# BNO055_SCH.net
KiCad netlist of a schematic drawn in EAGLE
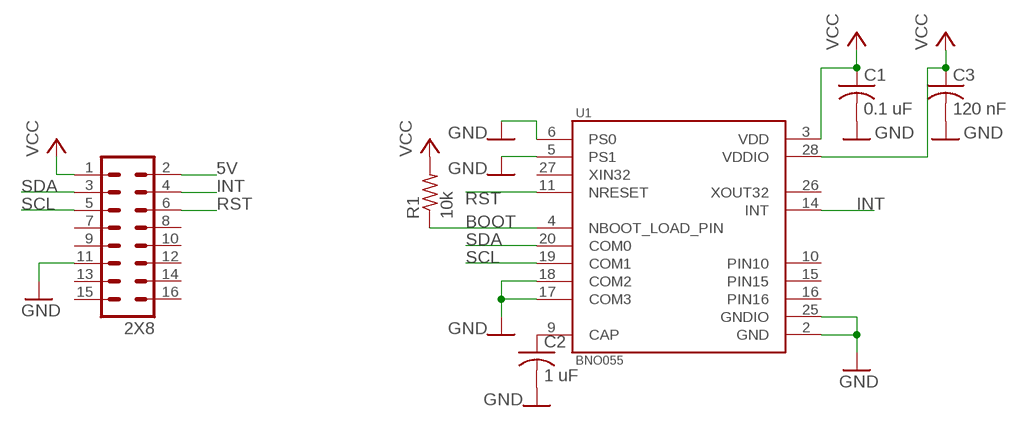
[diagram p0: schematic, sheet 1]

(export (version "E")
  (design (tool "Eeschema 10.0.6"))
  (components
    (comp (ref "2X8")
      (value "MA08-2")
      (footprint "eagle-import:MA08-2")
      (libsource (lib "eagle-import") (part "MA08-2"))
    )
    (comp (ref "C1")
      (value "0.1 uF")
      (footprint "eagle-import:C1206")
      (libsource (lib "eagle-import") (part "C-USC1206"))
    )
    (comp (ref "C2")
      (value "1 uF")
      (footprint "eagle-import:C1206")
      (libsource (lib "eagle-import") (part "C-USC1206"))
    )
    (comp (ref "C3")
      (value "120 nF")
      (footprint "eagle-import:C1206")
      (libsource (lib "eagle-import") (part "C-USC1206"))
    )
    (comp (ref "R1")
      (value "10k")
      (footprint "eagle-import:R1206")
      (libsource (lib "eagle-import") (part "R-US_R1206"))
    )
    (comp (ref "U1")
      (value "BNO055")
      (footprint "eagle-import:LGA28R50P4X10_380X520X100")
      (fields (field (name "MF") "Bosch"))
      (libsource (lib "eagle-import") (part "BNO055"))
    )
  )
  (nets
    (net (code "1") (name "/5V") (class "Default")
      (node (ref "2X8") (pin "2") (pinfunction "2_2") (pintype "passive"))
    )
    (net (code "2") (name "/BOOT") (class "Default")
      (node (ref "R1") (pin "1") (pinfunction "1_1") (pintype "passive"))
      (node (ref "U1") (pin "4") (pinfunction "NBOOT_LOAD_PIN_4") (pintype "bidirectional"))
    )
    (net (code "3") (name "/INT") (class "Default")
      (node (ref "2X8") (pin "4") (pinfunction "4_4") (pintype "passive"))
      (node (ref "U1") (pin "14") (pinfunction "INT_14") (pintype "output"))
    )
    (net (code "4") (name "/PIN10") (class "Default")
      (node (ref "U1") (pin "10") (pinfunction "PIN10_10") (pintype "power_in"))
    )
    (net (code "5") (name "/PIN15") (class "Default")
      (node (ref "U1") (pin "15") (pinfunction "PIN15_15") (pintype "power_in"))
    )
    (net (code "6") (name "/PIN16") (class "Default")
      (node (ref "U1") (pin "16") (pinfunction "PIN16_16") (pintype "power_in"))
    )
    (net (code "7") (name "/RST") (class "Default")
      (node (ref "2X8") (pin "6") (pinfunction "6_6") (pintype "passive"))
      (node (ref "U1") (pin "11") (pinfunction "NRESET_11") (pintype "input"))
    )
    (net (code "8") (name "/SCL") (class "Default")
      (node (ref "2X8") (pin "5") (pinfunction "5_5") (pintype "passive"))
      (node (ref "U1") (pin "19") (pinfunction "COM1_19") (pintype "bidirectional"))
    )
    (net (code "9") (name "/SDA") (class "Default")
      (node (ref "2X8") (pin "3") (pinfunction "3_3") (pintype "passive"))
      (node (ref "U1") (pin "20") (pinfunction "COM0_20") (pintype "bidirectional"))
    )
    (net (code "10") (name "GND") (class "Default")
      (node (ref "2X8") (pin "11") (pinfunction "11_11") (pintype "passive"))
      (node (ref "C1") (pin "2") (pinfunction "2_2") (pintype "passive"))
      (node (ref "C2") (pin "2") (pinfunction "2_2") (pintype "passive"))
      (node (ref "C3") (pin "2") (pinfunction "2_2") (pintype "passive"))
      (node (ref "U1") (pin "17") (pinfunction "COM3_17") (pintype "bidirectional"))
      (node (ref "U1") (pin "18") (pinfunction "COM2_18") (pintype "bidirectional"))
      (node (ref "U1") (pin "2") (pinfunction "GND_2") (pintype "power_in"))
      (node (ref "U1") (pin "25") (pinfunction "GNDIO_25") (pintype "power_in"))
      (node (ref "U1") (pin "5") (pinfunction "PS1_5") (pintype "input"))
      (node (ref "U1") (pin "6") (pinfunction "PS0_6") (pintype "input"))
    )
    (net (code "11") (name "Net-(U1-CAP)") (class "Default")
      (node (ref "C2") (pin "1") (pinfunction "1_1") (pintype "passive"))
      (node (ref "U1") (pin "9") (pinfunction "CAP_9") (pintype "passive"))
    )
    (net (code "12") (name "VCC") (class "Default")
      (node (ref "2X8") (pin "1") (pinfunction "1_1") (pintype "passive"))
      (node (ref "C1") (pin "1") (pinfunction "1_1") (pintype "passive"))
      (node (ref "C3") (pin "1") (pinfunction "1_1") (pintype "passive"))
      (node (ref "R1") (pin "2") (pinfunction "2_2") (pintype "passive"))
      (node (ref "U1") (pin "28") (pinfunction "VDDIO_28") (pintype "power_in"))
      (node (ref "U1") (pin "3") (pinfunction "VDD_3") (pintype "power_in"))
    )
    (net (code "13") (name "unconnected-(2X8-Pad7)") (class "Default")
      (node (ref "2X8") (pin "7") (pinfunction "7_7") (pintype "passive"))
    )
    (net (code "14") (name "unconnected-(2X8-Pad8)") (class "Default")
      (node (ref "2X8") (pin "8") (pinfunction "8_8") (pintype "passive"))
    )
    (net (code "15") (name "unconnected-(2X8-Pad9)") (class "Default")
      (node (ref "2X8") (pin "9") (pinfunction "9_9") (pintype "passive"))
    )
    (net (code "16") (name "unconnected-(2X8-Pad10)") (class "Default")
      (node (ref "2X8") (pin "10") (pinfunction "10_10") (pintype "passive"))
    )
    (net (code "17") (name "unconnected-(2X8-Pad12)") (class "Default")
      (node (ref "2X8") (pin "12") (pinfunction "12_12") (pintype "passive"))
    )
    (net (code "18") (name "unconnected-(2X8-Pad13)") (class "Default")
      (node (ref "2X8") (pin "13") (pinfunction "13_13") (pintype "passive"))
    )
    (net (code "19") (name "unconnected-(2X8-Pad14)") (class "Default")
      (node (ref "2X8") (pin "14") (pinfunction "14_14") (pintype "passive"))
    )
    (net (code "20") (name "unconnected-(2X8-Pad15)") (class "Default")
      (node (ref "2X8") (pin "15") (pinfunction "15_15") (pintype "passive"))
    )
    (net (code "21") (name "unconnected-(2X8-Pad16)") (class "Default")
      (node (ref "2X8") (pin "16") (pinfunction "16_16") (pintype "passive"))
    )
    (net (code "22") (name "unconnected-(U1-XIN32-Pad27)") (class "Default")
      (node (ref "U1") (pin "27") (pinfunction "XIN32_27") (pintype "input"))
    )
    (net (code "23") (name "unconnected-(U1-XOUT32-Pad26)") (class "Default")
      (node (ref "U1") (pin "26") (pinfunction "XOUT32_26") (pintype "output"))
    )
  )
)
